# 20KV_Diode.net
KiCad netlist of a schematic drawn in EAGLE
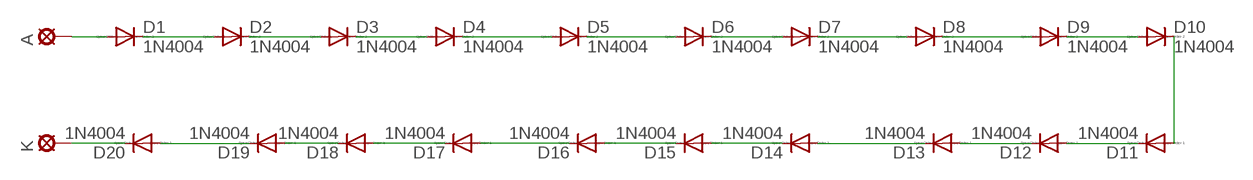
[diagram p0: schematic, sheet 1]

(export (version "E")
  (design (tool "Eeschema 10.0.6"))
  (components
    (comp (ref "A")
      (value "LSP10")
      (footprint "eagle-import:LSP10")
      (libsource (lib "eagle-import") (part "LSP10"))
    )
    (comp (ref "D1")
      (value "1N4004")
      (footprint "eagle-import:DO41-10")
      (libsource (lib "eagle-import") (part "1N4004"))
    )
    (comp (ref "D2")
      (value "1N4004")
      (footprint "eagle-import:DO41-10")
      (libsource (lib "eagle-import") (part "1N4004"))
    )
    (comp (ref "D3")
      (value "1N4004")
      (footprint "eagle-import:DO41-10")
      (libsource (lib "eagle-import") (part "1N4004"))
    )
    (comp (ref "D4")
      (value "1N4004")
      (footprint "eagle-import:DO41-10")
      (libsource (lib "eagle-import") (part "1N4004"))
    )
    (comp (ref "D5")
      (value "1N4004")
      (footprint "eagle-import:DO41-10")
      (libsource (lib "eagle-import") (part "1N4004"))
    )
    (comp (ref "D6")
      (value "1N4004")
      (footprint "eagle-import:DO41-10")
      (libsource (lib "eagle-import") (part "1N4004"))
    )
    (comp (ref "D7")
      (value "1N4004")
      (footprint "eagle-import:DO41-10")
      (libsource (lib "eagle-import") (part "1N4004"))
    )
    (comp (ref "D8")
      (value "1N4004")
      (footprint "eagle-import:DO41-10")
      (libsource (lib "eagle-import") (part "1N4004"))
    )
    (comp (ref "D9")
      (value "1N4004")
      (footprint "eagle-import:DO41-10")
      (libsource (lib "eagle-import") (part "1N4004"))
    )
    (comp (ref "D10")
      (value "1N4004")
      (footprint "eagle-import:DO41-10")
      (libsource (lib "eagle-import") (part "1N4004"))
    )
    (comp (ref "D11")
      (value "1N4004")
      (footprint "eagle-import:DO41-10")
      (libsource (lib "eagle-import") (part "1N4004"))
    )
    (comp (ref "D12")
      (value "1N4004")
      (footprint "eagle-import:DO41-10")
      (libsource (lib "eagle-import") (part "1N4004"))
    )
    (comp (ref "D13")
      (value "1N4004")
      (footprint "eagle-import:DO41-10")
      (libsource (lib "eagle-import") (part "1N4004"))
    )
    (comp (ref "D14")
      (value "1N4004")
      (footprint "eagle-import:DO41-10")
      (libsource (lib "eagle-import") (part "1N4004"))
    )
    (comp (ref "D15")
      (value "1N4004")
      (footprint "eagle-import:DO41-10")
      (libsource (lib "eagle-import") (part "1N4004"))
    )
    (comp (ref "D16")
      (value "1N4004")
      (footprint "eagle-import:DO41-10")
      (libsource (lib "eagle-import") (part "1N4004"))
    )
    (comp (ref "D17")
      (value "1N4004")
      (footprint "eagle-import:DO41-10")
      (libsource (lib "eagle-import") (part "1N4004"))
    )
    (comp (ref "D18")
      (value "1N4004")
      (footprint "eagle-import:DO41-10")
      (libsource (lib "eagle-import") (part "1N4004"))
    )
    (comp (ref "D19")
      (value "1N4004")
      (footprint "eagle-import:DO41-10")
      (libsource (lib "eagle-import") (part "1N4004"))
    )
    (comp (ref "D20")
      (value "1N4004")
      (footprint "eagle-import:DO41-10")
      (libsource (lib "eagle-import") (part "1N4004"))
    )
    (comp (ref "K")
      (value "LSP10")
      (footprint "eagle-import:LSP10")
      (libsource (lib "eagle-import") (part "LSP10"))
    )
  )
  (nets
    (net (code "1") (name "Net-(A-PadMP)") (class "Default")
      (node (ref "A") (pin "MP") (pinfunction "MP_MP") (pintype "passive"))
      (node (ref "D1") (pin "A") (pinfunction "A_A") (pintype "passive"))
    )
    (net (code "2") (name "Net-(D1-PadC)") (class "Default")
      (node (ref "D1") (pin "C") (pinfunction "C_C") (pintype "passive"))
      (node (ref "D2") (pin "A") (pinfunction "A_A") (pintype "passive"))
    )
    (net (code "3") (name "Net-(D2-PadC)") (class "Default")
      (node (ref "D2") (pin "C") (pinfunction "C_C") (pintype "passive"))
      (node (ref "D3") (pin "A") (pinfunction "A_A") (pintype "passive"))
    )
    (net (code "4") (name "Net-(D3-PadC)") (class "Default")
      (node (ref "D3") (pin "C") (pinfunction "C_C") (pintype "passive"))
      (node (ref "D4") (pin "A") (pinfunction "A_A") (pintype "passive"))
    )
    (net (code "5") (name "Net-(D4-PadC)") (class "Default")
      (node (ref "D4") (pin "C") (pinfunction "C_C") (pintype "passive"))
      (node (ref "D5") (pin "A") (pinfunction "A_A") (pintype "passive"))
    )
    (net (code "6") (name "Net-(D5-PadC)") (class "Default")
      (node (ref "D5") (pin "C") (pinfunction "C_C") (pintype "passive"))
      (node (ref "D6") (pin "A") (pinfunction "A_A") (pintype "passive"))
    )
    (net (code "7") (name "Net-(D6-PadC)") (class "Default")
      (node (ref "D6") (pin "C") (pinfunction "C_C") (pintype "passive"))
      (node (ref "D7") (pin "A") (pinfunction "A_A") (pintype "passive"))
    )
    (net (code "8") (name "Net-(D7-PadC)") (class "Default")
      (node (ref "D7") (pin "C") (pinfunction "C_C") (pintype "passive"))
      (node (ref "D8") (pin "A") (pinfunction "A_A") (pintype "passive"))
    )
    (net (code "9") (name "Net-(D8-PadC)") (class "Default")
      (node (ref "D8") (pin "C") (pinfunction "C_C") (pintype "passive"))
      (node (ref "D9") (pin "A") (pinfunction "A_A") (pintype "passive"))
    )
    (net (code "10") (name "Net-(D10-PadA)") (class "Default")
      (node (ref "D10") (pin "A") (pinfunction "A_A") (pintype "passive"))
      (node (ref "D9") (pin "C") (pinfunction "C_C") (pintype "passive"))
    )
    (net (code "11") (name "Net-(D10-PadC)") (class "Default")
      (node (ref "D10") (pin "C") (pinfunction "C_C") (pintype "passive"))
      (node (ref "D11") (pin "A") (pinfunction "A_A") (pintype "passive"))
    )
    (net (code "12") (name "Net-(D11-PadC)") (class "Default")
      (node (ref "D11") (pin "C") (pinfunction "C_C") (pintype "passive"))
      (node (ref "D12") (pin "A") (pinfunction "A_A") (pintype "passive"))
    )
    (net (code "13") (name "Net-(D12-PadC)") (class "Default")
      (node (ref "D12") (pin "C") (pinfunction "C_C") (pintype "passive"))
      (node (ref "D13") (pin "A") (pinfunction "A_A") (pintype "passive"))
    )
    (net (code "14") (name "Net-(D13-PadC)") (class "Default")
      (node (ref "D13") (pin "C") (pinfunction "C_C") (pintype "passive"))
      (node (ref "D14") (pin "A") (pinfunction "A_A") (pintype "passive"))
    )
    (net (code "15") (name "Net-(D14-PadC)") (class "Default")
      (node (ref "D14") (pin "C") (pinfunction "C_C") (pintype "passive"))
      (node (ref "D15") (pin "A") (pinfunction "A_A") (pintype "passive"))
    )
    (net (code "16") (name "Net-(D15-PadC)") (class "Default")
      (node (ref "D15") (pin "C") (pinfunction "C_C") (pintype "passive"))
      (node (ref "D16") (pin "A") (pinfunction "A_A") (pintype "passive"))
    )
    (net (code "17") (name "Net-(D16-PadC)") (class "Default")
      (node (ref "D16") (pin "C") (pinfunction "C_C") (pintype "passive"))
      (node (ref "D17") (pin "A") (pinfunction "A_A") (pintype "passive"))
    )
    (net (code "18") (name "Net-(D17-PadC)") (class "Default")
      (node (ref "D17") (pin "C") (pinfunction "C_C") (pintype "passive"))
      (node (ref "D18") (pin "A") (pinfunction "A_A") (pintype "passive"))
    )
    (net (code "19") (name "Net-(D18-PadC)") (class "Default")
      (node (ref "D18") (pin "C") (pinfunction "C_C") (pintype "passive"))
      (node (ref "D19") (pin "A") (pinfunction "A_A") (pintype "passive"))
    )
    (net (code "20") (name "Net-(D19-PadC)") (class "Default")
      (node (ref "D19") (pin "C") (pinfunction "C_C") (pintype "passive"))
      (node (ref "D20") (pin "A") (pinfunction "A_A") (pintype "passive"))
    )
    (net (code "21") (name "Net-(D20-PadC)") (class "Default")
      (node (ref "D20") (pin "C") (pinfunction "C_C") (pintype "passive"))
      (node (ref "K") (pin "MP") (pinfunction "MP_MP") (pintype "passive"))
    )
  )
)
